# SCH_primary_recovery_n-3_board_2022-10-1.net
KiCad netlist of a schematic drawn in EasyEDA
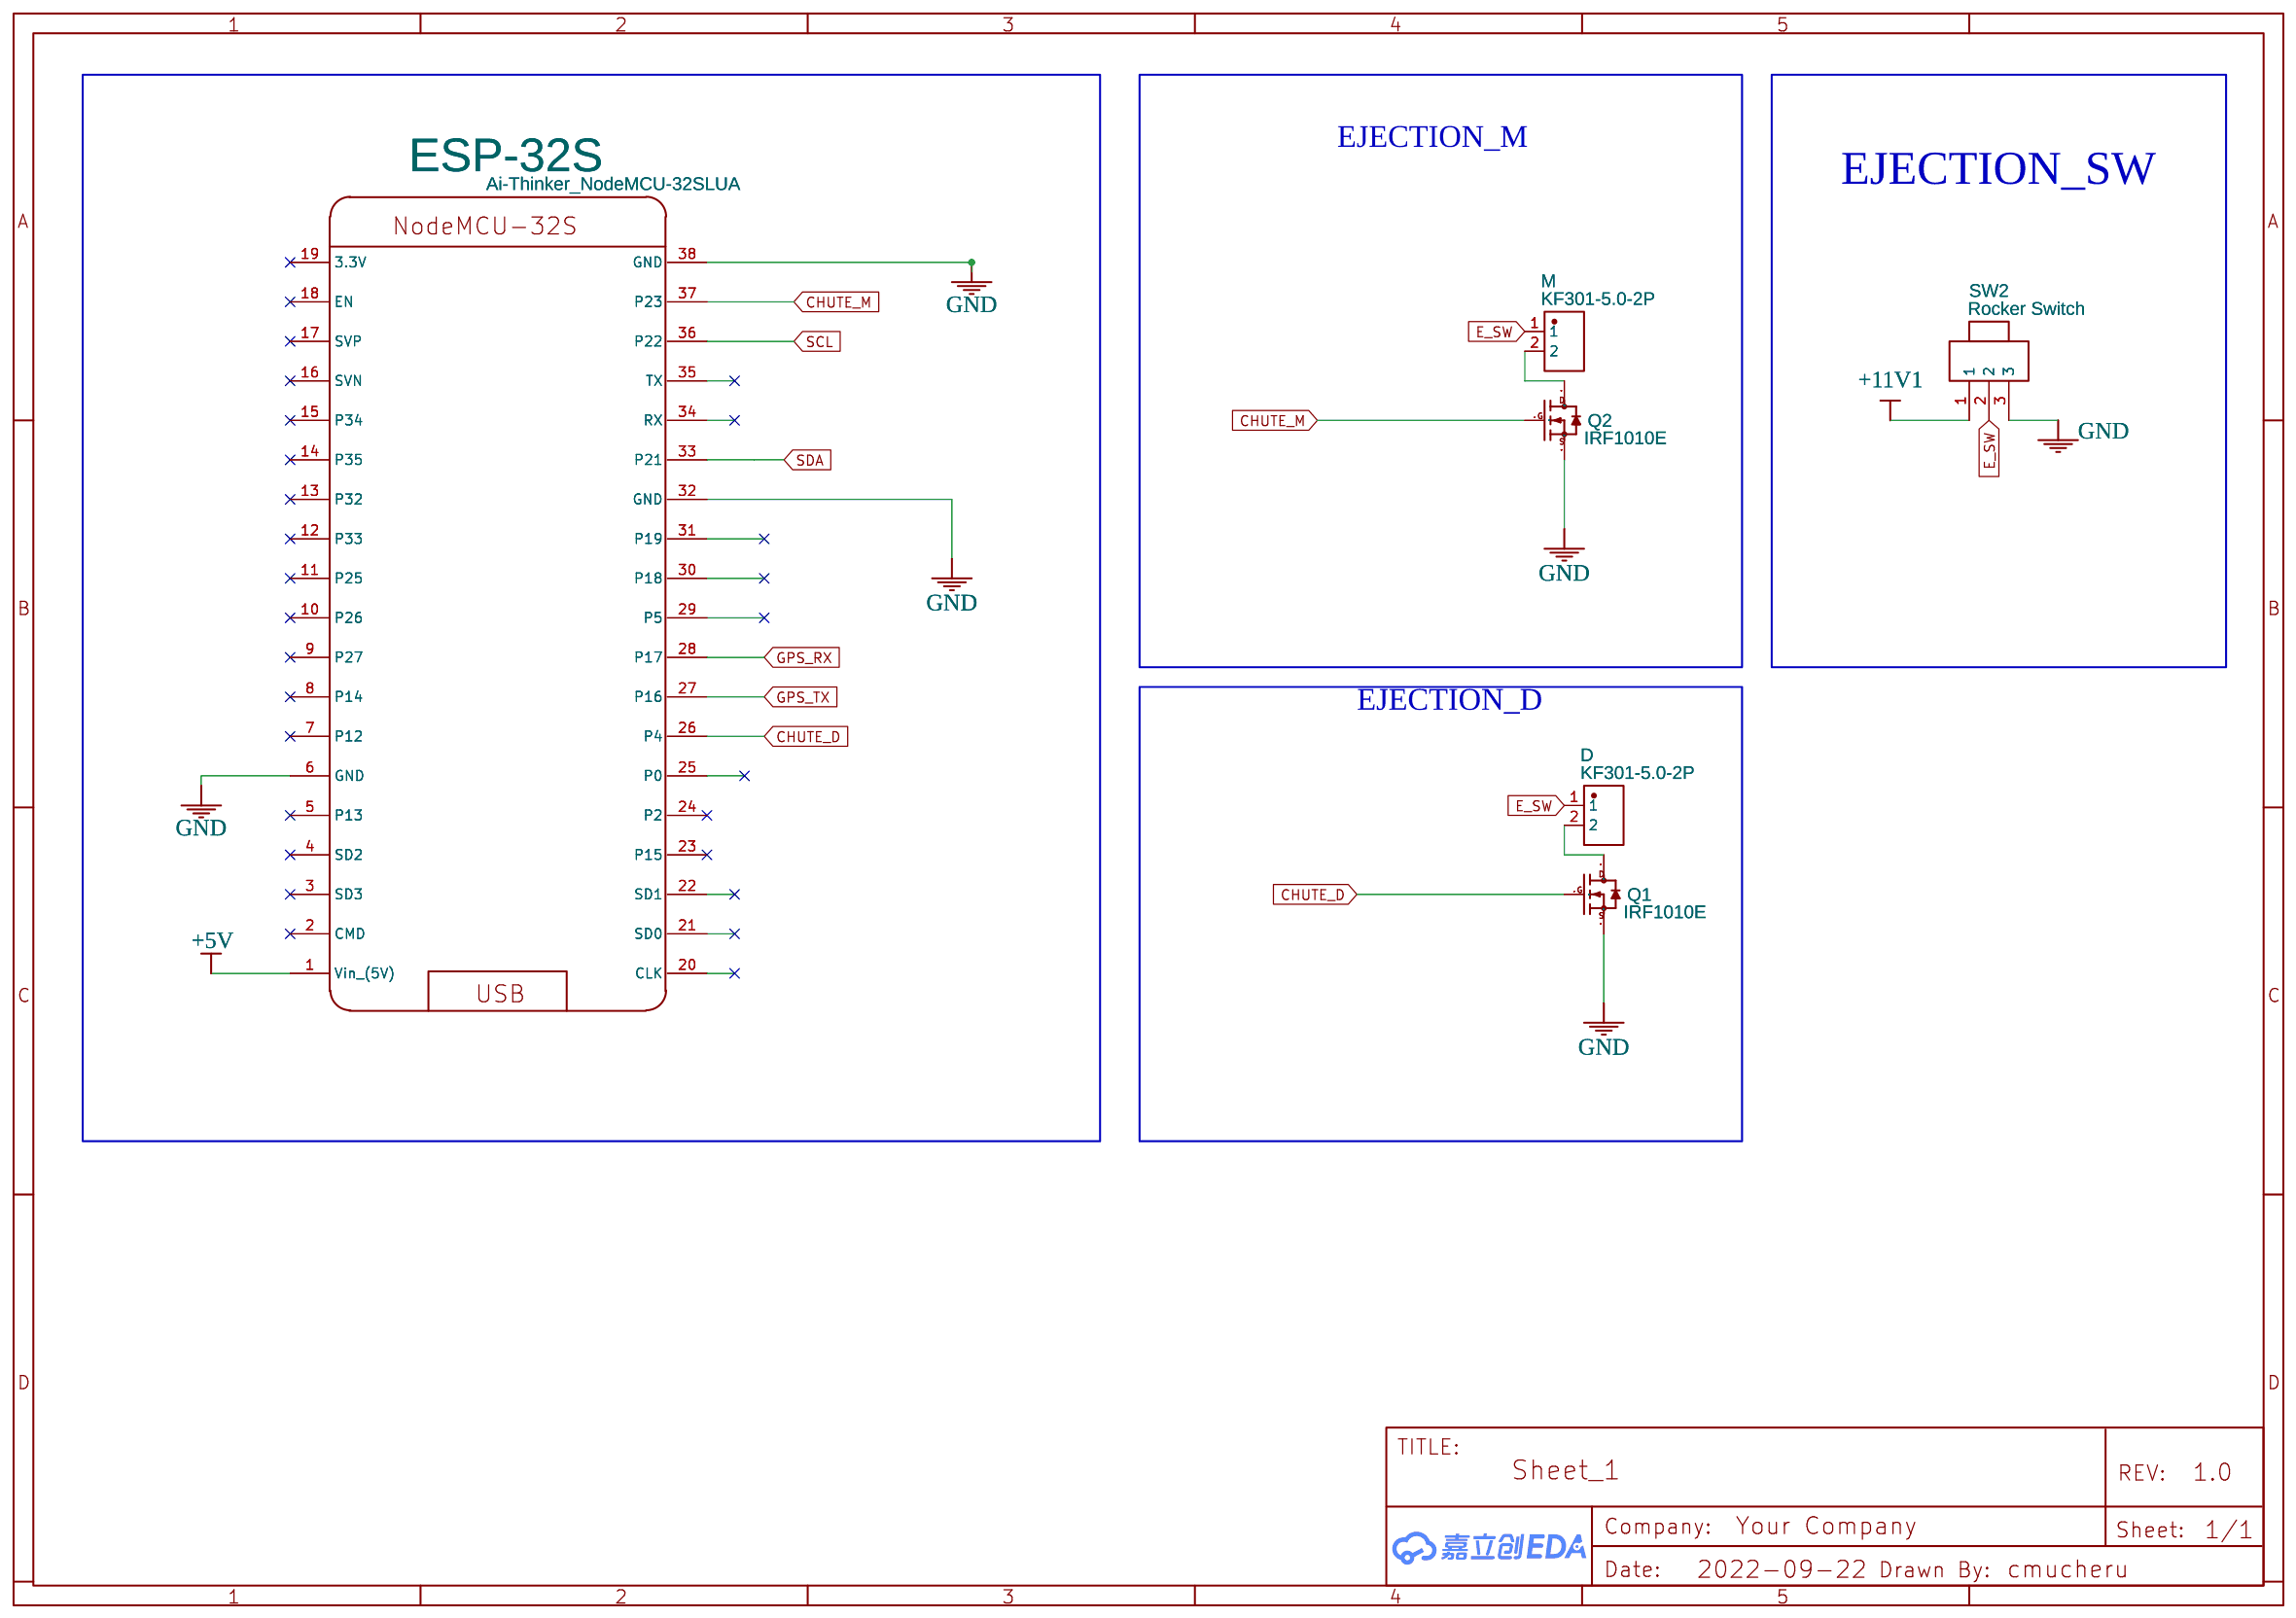
[diagram p0: Sheet_1]
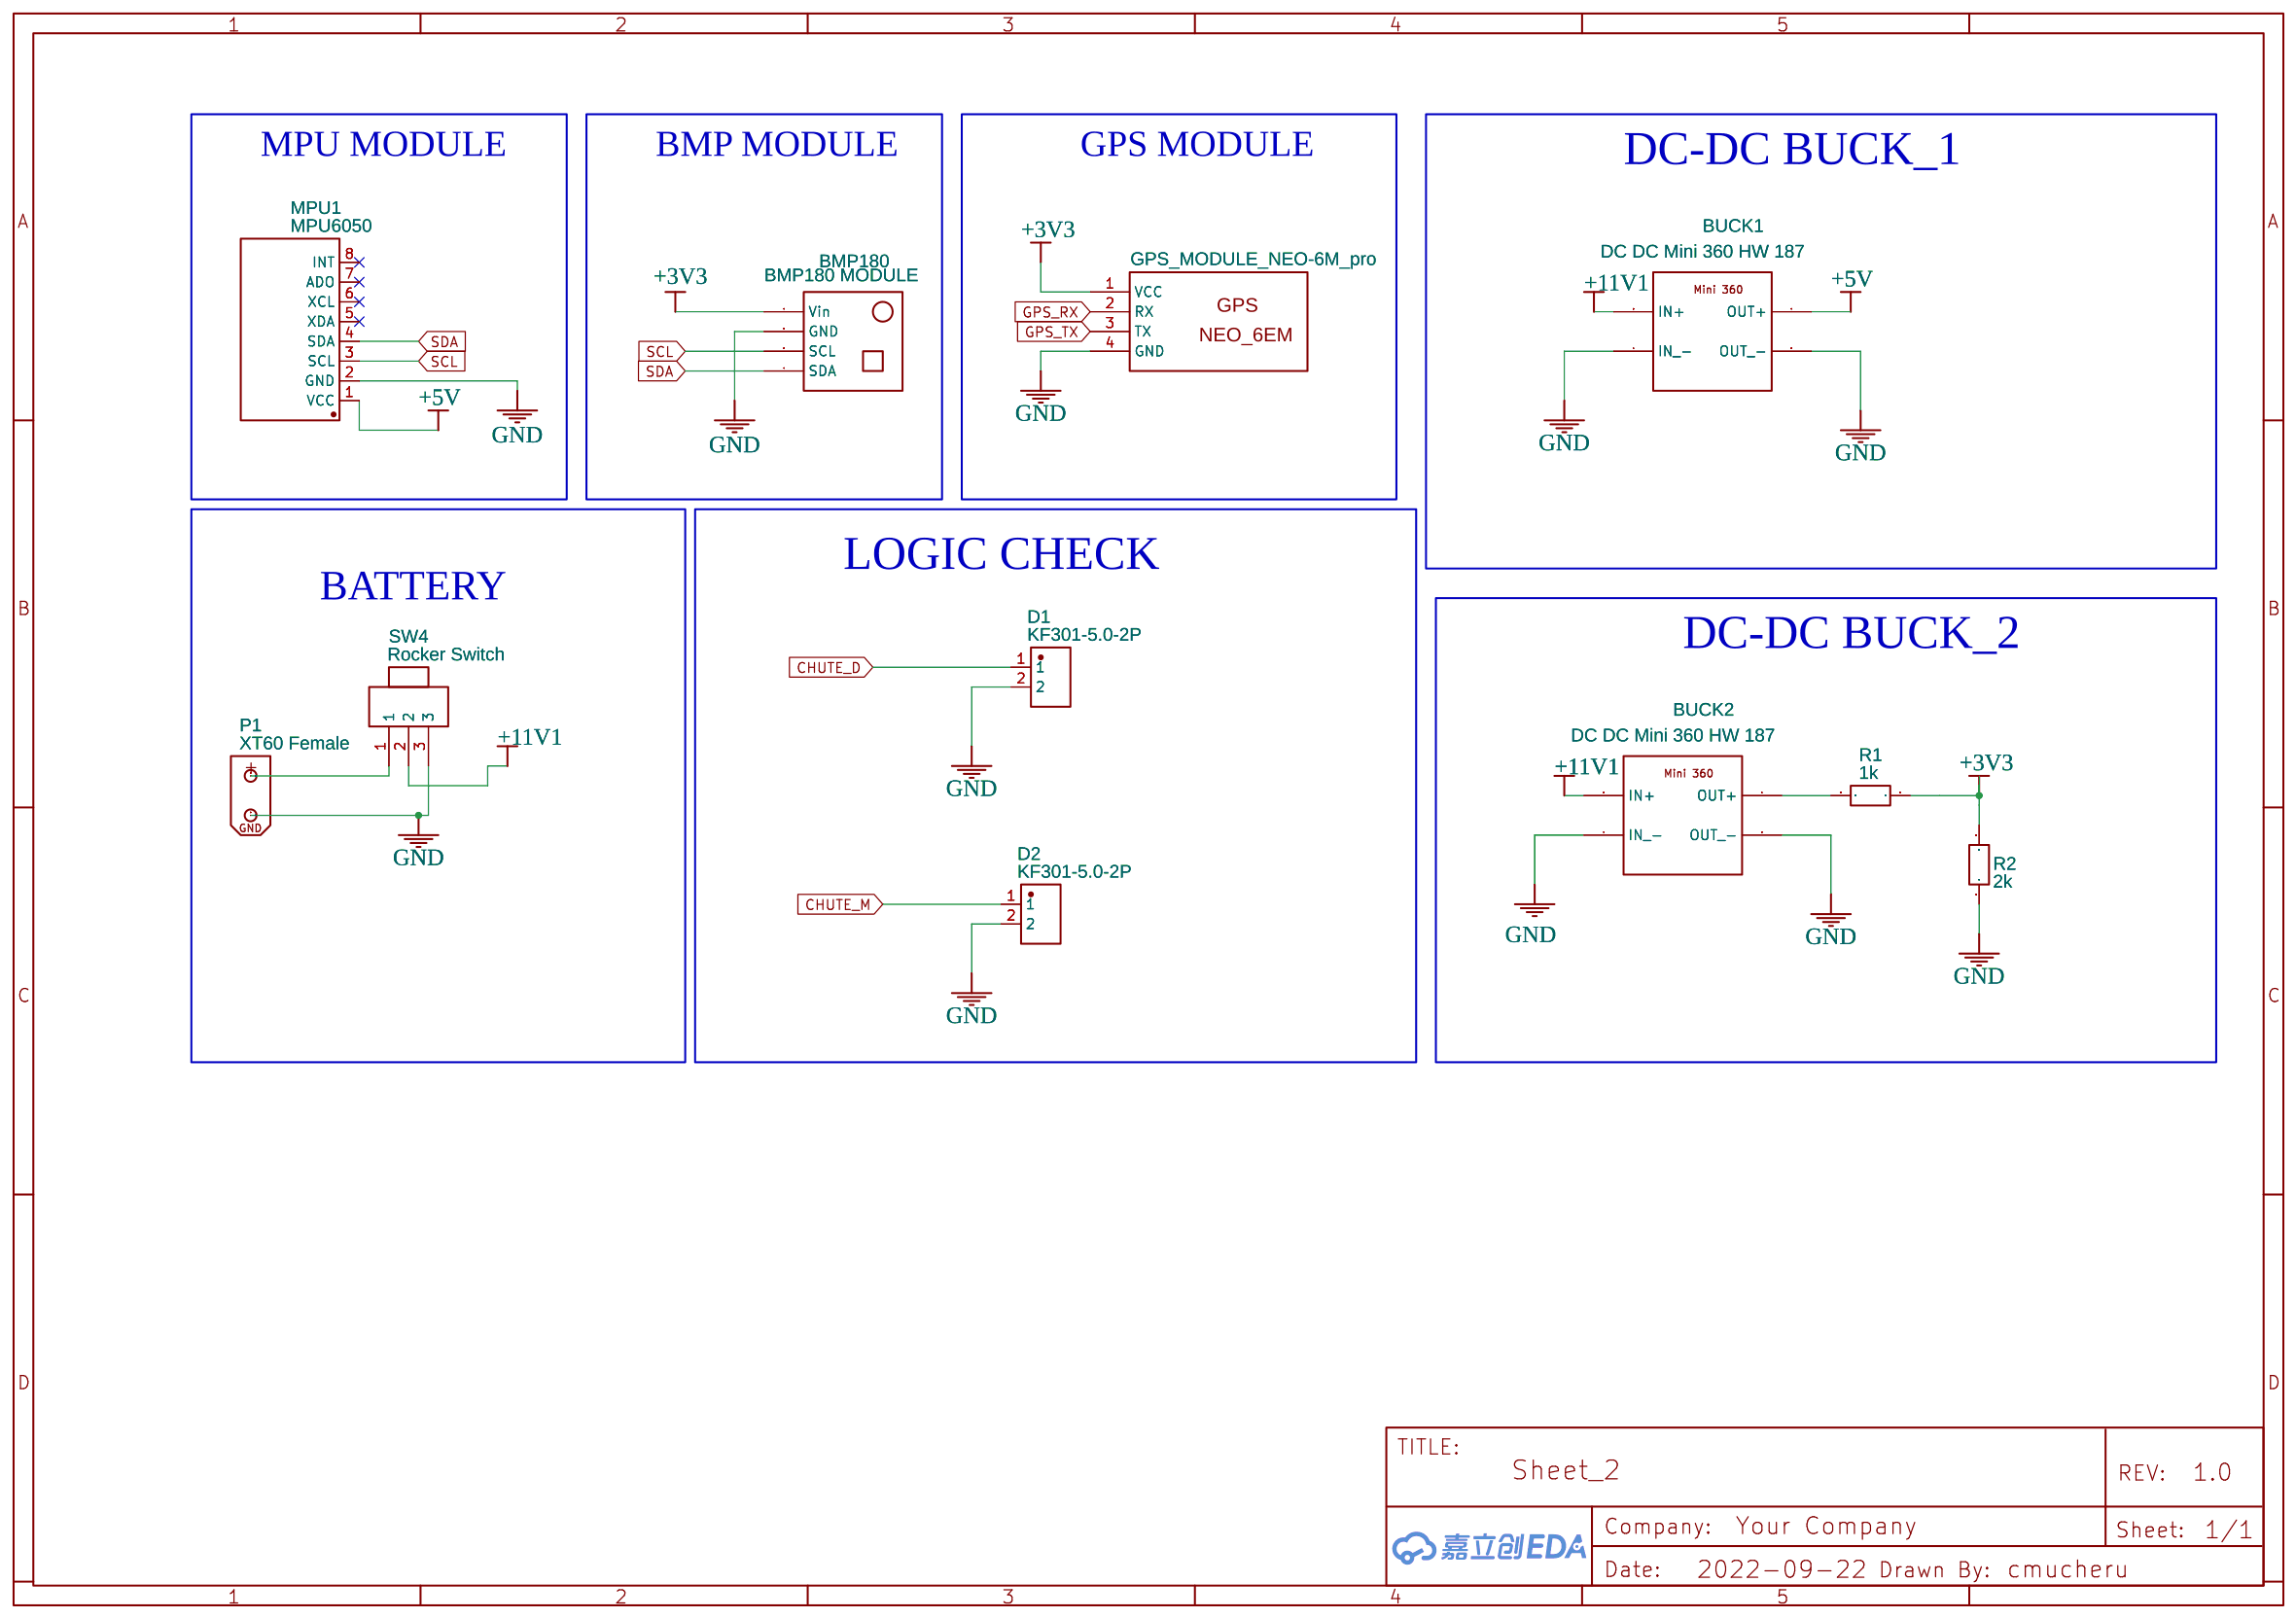
[diagram p1: Sheet_2]

(export (version "E")
  (design (tool "Eeschema 10.0.6"))
  (components
    (comp (ref "D")
      (value "KF301-5.0-2P")
      (fields (field (name "BOM_Supplier Part") "C474881"))
      (libsource (lib "") (part "KF301-5.0-2P_1"))
    )
    (comp (ref "ESP-32S")
      (value "Ai-Thinker_NodeMCU-32SLUA")
      (fields
        (field (name "BOM_Manufacturer Part") "NodeMCU-32SLua")
        (field (name "BOM_Supplier Part") "C111436")
      )
      (libsource (lib "") (part "Ai-Thinker_NodeMCU-32SLUA"))
    )
    (comp (ref "M")
      (value "KF301-5.0-2P")
      (fields (field (name "BOM_Supplier Part") "C474881"))
      (libsource (lib "") (part "KF301-5.0-2P"))
    )
    (comp (ref "Q1") (value "IRF1010E") (libsource (lib "") (part "Mosfet-N")))
    (comp (ref "Q2") (value "IRF1010E") (libsource (lib "") (part "Mosfet-N")))
    (comp (ref "SW2") (value "Rocker Switch") (libsource (lib "") (part "Rocker Switch")))
    (comp (ref "BMP180")
      (value "BMP180 MODULE")
      (fields (field (name "BOM_Manufacturer Part") "BMP180 (HW-596)"))
      (libsource (lib "") (part "BMP180 MODULE"))
    )
    (comp (ref "BUCK1") (value "DC DC Mini 360 HW 187") (libsource (lib "") (part "DC DC Mini 360 HW 187")))
    (comp (ref "BUCK2") (value "DC DC Mini 360 HW 187") (libsource (lib "") (part "DC DC Mini 360 HW 187")))
    (comp (ref "D1")
      (value "KF301-5.0-2P")
      (fields (field (name "BOM_Supplier Part") "C474881"))
      (libsource (lib "") (part "KF301-5.0-2P"))
    )
    (comp (ref "D2")
      (value "KF301-5.0-2P")
      (fields (field (name "BOM_Supplier Part") "C474881"))
      (libsource (lib "") (part "KF301-5.0-2P"))
    )
    (comp (ref "GPS_NEO-2EM")
      (value "GPS_MODULE_NEO-6M_pro")
      (libsource (lib "") (part "GPS_MODULE_NEO-6M_pro"))
    )
    (comp (ref "MPU1")
      (value "MPU6050")
      (fields (field (name "BOM_Supplier Part") "GY521"))
      (libsource (lib "") (part "MPU6050"))
    )
    (comp (ref "P1")
      (value "XT60 Female")
      (fields (field (name "BOM_Manufacturer Part") "XT60-F"))
      (libsource (lib "") (part "XT60 Female"))
    )
    (comp (ref "R1")
      (value "1k")
      (fields (field (name "BOM_Manufacturer Part") "OD684JE") (field (name "BOM_Supplier Part") "C3527706"))
      (libsource (lib "") (part "OD684JE_1"))
    )
    (comp (ref "R2")
      (value "2k")
      (fields (field (name "BOM_Manufacturer Part") "OD684JE") (field (name "BOM_Supplier Part") "C3527706"))
      (libsource (lib "") (part "OD684JE"))
    )
    (comp (ref "SW4") (value "Rocker Switch") (libsource (lib "") (part "Rocker Switch")))
  )
  (nets
    (net (code "1") (name "+3V3") (class "Default")
      (node (ref "BMP180") (pin "1") (pinfunction "Vin_1") (pintype "unspecified"))
      (node (ref "GPS_NEO-2EM") (pin "1") (pinfunction "VCC_1") (pintype "passive"))
      (node (ref "R1") (pin "1") (pinfunction "1_1") (pintype "unspecified"))
      (node (ref "R2") (pin "2") (pinfunction "2_2") (pintype "unspecified"))
    )
    (net (code "2") (name "+5V") (class "Default")
      (node (ref "BUCK1") (pin "1") (pinfunction "OUT+_1") (pintype "unspecified"))
      (node (ref "ESP-32S") (pin "1") (pinfunction "Vin_(5V)_1") (pintype "unspecified"))
      (node (ref "MPU1") (pin "1") (pinfunction "VCC_1") (pintype "unspecified"))
    )
    (net (code "3") (name "+11V1") (class "Default")
      (node (ref "BUCK1") (pin "3") (pinfunction "IN+_3") (pintype "unspecified"))
      (node (ref "BUCK2") (pin "3") (pinfunction "IN+_3") (pintype "unspecified"))
      (node (ref "SW2") (pin "1") (pinfunction "1_1") (pintype "unspecified"))
      (node (ref "SW4") (pin "2") (pinfunction "2_2") (pintype "unspecified"))
    )
    (net (code "4") (name "CHUTE_D") (class "Default")
      (node (ref "D1") (pin "1") (pinfunction "1_1") (pintype "unspecified"))
      (node (ref "ESP-32S") (pin "26") (pinfunction "P4_26") (pintype "unspecified"))
      (node (ref "Q1") (pin "1") (pinfunction "G_1") (pintype "unspecified"))
    )
    (net (code "5") (name "CHUTE_M") (class "Default")
      (node (ref "D2") (pin "1") (pinfunction "1_1") (pintype "unspecified"))
      (node (ref "ESP-32S") (pin "37") (pinfunction "P23_37") (pintype "unspecified"))
      (node (ref "Q2") (pin "1") (pinfunction "G_1") (pintype "unspecified"))
    )
    (net (code "6") (name "E_SW") (class "Default")
      (node (ref "D") (pin "1") (pinfunction "1_1") (pintype "unspecified"))
      (node (ref "M") (pin "1") (pinfunction "1_1") (pintype "unspecified"))
      (node (ref "SW2") (pin "2") (pinfunction "2_2") (pintype "unspecified"))
    )
    (net (code "7") (name "GND") (class "Default")
      (node (ref "BMP180") (pin "2") (pinfunction "GND_2") (pintype "unspecified"))
      (node (ref "BUCK1") (pin "2") (pinfunction "OUT_-_2") (pintype "unspecified"))
      (node (ref "BUCK1") (pin "4") (pinfunction "IN_-_4") (pintype "unspecified"))
      (node (ref "BUCK2") (pin "2") (pinfunction "OUT_-_2") (pintype "unspecified"))
      (node (ref "BUCK2") (pin "4") (pinfunction "IN_-_4") (pintype "unspecified"))
      (node (ref "D1") (pin "2") (pinfunction "2_2") (pintype "unspecified"))
      (node (ref "D2") (pin "2") (pinfunction "2_2") (pintype "unspecified"))
      (node (ref "ESP-32S") (pin "32") (pinfunction "GND_32") (pintype "unspecified"))
      (node (ref "ESP-32S") (pin "38") (pinfunction "GND_38") (pintype "unspecified"))
      (node (ref "ESP-32S") (pin "6") (pinfunction "GND_6") (pintype "unspecified"))
      (node (ref "GPS_NEO-2EM") (pin "4") (pinfunction "GND_4") (pintype "passive"))
      (node (ref "MPU1") (pin "2") (pinfunction "GND_2") (pintype "unspecified"))
      (node (ref "P1") (pin "1") (pinfunction "1_1") (pintype "unspecified"))
      (node (ref "Q1") (pin "3") (pinfunction "S_3") (pintype "unspecified"))
      (node (ref "Q2") (pin "3") (pinfunction "S_3") (pintype "unspecified"))
      (node (ref "R2") (pin "1") (pinfunction "1_1") (pintype "unspecified"))
      (node (ref "SW2") (pin "3") (pinfunction "3_3") (pintype "unspecified"))
      (node (ref "SW4") (pin "3") (pinfunction "3_3") (pintype "unspecified"))
    )
    (net (code "8") (name "GPS_RX") (class "Default")
      (node (ref "ESP-32S") (pin "28") (pinfunction "P17_28") (pintype "unspecified"))
      (node (ref "GPS_NEO-2EM") (pin "2") (pinfunction "RX_2") (pintype "input"))
    )
    (net (code "9") (name "GPS_TX") (class "Default")
      (node (ref "ESP-32S") (pin "27") (pinfunction "P16_27") (pintype "unspecified"))
      (node (ref "GPS_NEO-2EM") (pin "3") (pinfunction "TX_3") (pintype "output"))
    )
    (net (code "10") (name "Net-(BUCK2-OUT+)") (class "Default")
      (node (ref "BUCK2") (pin "1") (pinfunction "OUT+_1") (pintype "unspecified"))
      (node (ref "R1") (pin "2") (pinfunction "2_2") (pintype "unspecified"))
    )
    (net (code "11") (name "Net-(P1-Pad2)") (class "Default")
      (node (ref "P1") (pin "2") (pinfunction "2_2") (pintype "unspecified"))
      (node (ref "SW4") (pin "1") (pinfunction "1_1") (pintype "unspecified"))
    )
    (net (code "12") (name "Net-(Q1-D)") (class "Default")
      (node (ref "D") (pin "2") (pinfunction "2_2") (pintype "unspecified"))
      (node (ref "Q1") (pin "2") (pinfunction "D_2") (pintype "unspecified"))
    )
    (net (code "13") (name "Net-(Q2-D)") (class "Default")
      (node (ref "M") (pin "2") (pinfunction "2_2") (pintype "unspecified"))
      (node (ref "Q2") (pin "2") (pinfunction "D_2") (pintype "unspecified"))
    )
    (net (code "14") (name "SCL") (class "Default")
      (node (ref "BMP180") (pin "3") (pinfunction "SCL_3") (pintype "unspecified"))
      (node (ref "ESP-32S") (pin "36") (pinfunction "P22_36") (pintype "unspecified"))
      (node (ref "MPU1") (pin "3") (pinfunction "SCL_3") (pintype "unspecified"))
    )
    (net (code "15") (name "SDA") (class "Default")
      (node (ref "BMP180") (pin "4") (pinfunction "SDA_4") (pintype "unspecified"))
      (node (ref "ESP-32S") (pin "33") (pinfunction "P21_33") (pintype "unspecified"))
      (node (ref "MPU1") (pin "4") (pinfunction "SDA_4") (pintype "unspecified"))
    )
    (net (code "16") (name "unconnected-(ESP-32S-3.3V-Pad19)") (class "Default")
      (node (ref "ESP-32S") (pin "19") (pinfunction "3.3V_19") (pintype "unspecified+no_connect"))
    )
    (net (code "17") (name "unconnected-(ESP-32S-CLK-Pad20)") (class "Default")
      (node (ref "ESP-32S") (pin "20") (pinfunction "CLK_20") (pintype "unspecified+no_connect"))
    )
    (net (code "18") (name "unconnected-(ESP-32S-CMD-Pad2)") (class "Default")
      (node (ref "ESP-32S") (pin "2") (pinfunction "CMD_2") (pintype "unspecified+no_connect"))
    )
    (net (code "19") (name "unconnected-(ESP-32S-EN-Pad18)") (class "Default")
      (node (ref "ESP-32S") (pin "18") (pinfunction "EN_18") (pintype "unspecified+no_connect"))
    )
    (net (code "20") (name "unconnected-(ESP-32S-P0-Pad25)") (class "Default")
      (node (ref "ESP-32S") (pin "25") (pinfunction "P0_25") (pintype "unspecified+no_connect"))
    )
    (net (code "21") (name "unconnected-(ESP-32S-P2-Pad24)") (class "Default")
      (node (ref "ESP-32S") (pin "24") (pinfunction "P2_24") (pintype "unspecified+no_connect"))
    )
    (net (code "22") (name "unconnected-(ESP-32S-P5-Pad29)") (class "Default")
      (node (ref "ESP-32S") (pin "29") (pinfunction "P5_29") (pintype "unspecified+no_connect"))
    )
    (net (code "23") (name "unconnected-(ESP-32S-P12-Pad7)") (class "Default")
      (node (ref "ESP-32S") (pin "7") (pinfunction "P12_7") (pintype "unspecified+no_connect"))
    )
    (net (code "24") (name "unconnected-(ESP-32S-P13-Pad5)") (class "Default")
      (node (ref "ESP-32S") (pin "5") (pinfunction "P13_5") (pintype "unspecified+no_connect"))
    )
    (net (code "25") (name "unconnected-(ESP-32S-P14-Pad8)") (class "Default")
      (node (ref "ESP-32S") (pin "8") (pinfunction "P14_8") (pintype "unspecified+no_connect"))
    )
    (net (code "26") (name "unconnected-(ESP-32S-P15-Pad23)") (class "Default")
      (node (ref "ESP-32S") (pin "23") (pinfunction "P15_23") (pintype "unspecified+no_connect"))
    )
    (net (code "27") (name "unconnected-(ESP-32S-P18-Pad30)") (class "Default")
      (node (ref "ESP-32S") (pin "30") (pinfunction "P18_30") (pintype "unspecified+no_connect"))
    )
    (net (code "28") (name "unconnected-(ESP-32S-P19-Pad31)") (class "Default")
      (node (ref "ESP-32S") (pin "31") (pinfunction "P19_31") (pintype "unspecified+no_connect"))
    )
    (net (code "29") (name "unconnected-(ESP-32S-P25-Pad11)") (class "Default")
      (node (ref "ESP-32S") (pin "11") (pinfunction "P25_11") (pintype "unspecified+no_connect"))
    )
    (net (code "30") (name "unconnected-(ESP-32S-P26-Pad10)") (class "Default")
      (node (ref "ESP-32S") (pin "10") (pinfunction "P26_10") (pintype "unspecified+no_connect"))
    )
    (net (code "31") (name "unconnected-(ESP-32S-P27-Pad9)") (class "Default")
      (node (ref "ESP-32S") (pin "9") (pinfunction "P27_9") (pintype "unspecified+no_connect"))
    )
    (net (code "32") (name "unconnected-(ESP-32S-P32-Pad13)") (class "Default")
      (node (ref "ESP-32S") (pin "13") (pinfunction "P32_13") (pintype "unspecified+no_connect"))
    )
    (net (code "33") (name "unconnected-(ESP-32S-P33-Pad12)") (class "Default")
      (node (ref "ESP-32S") (pin "12") (pinfunction "P33_12") (pintype "unspecified+no_connect"))
    )
    (net (code "34") (name "unconnected-(ESP-32S-P34-Pad15)") (class "Default")
      (node (ref "ESP-32S") (pin "15") (pinfunction "P34_15") (pintype "unspecified+no_connect"))
    )
    (net (code "35") (name "unconnected-(ESP-32S-P35-Pad14)") (class "Default")
      (node (ref "ESP-32S") (pin "14") (pinfunction "P35_14") (pintype "unspecified+no_connect"))
    )
    (net (code "36") (name "unconnected-(ESP-32S-RX-Pad34)") (class "Default")
      (node (ref "ESP-32S") (pin "34") (pinfunction "RX_34") (pintype "unspecified+no_connect"))
    )
    (net (code "37") (name "unconnected-(ESP-32S-SD0-Pad21)") (class "Default")
      (node (ref "ESP-32S") (pin "21") (pinfunction "SD0_21") (pintype "unspecified+no_connect"))
    )
    (net (code "38") (name "unconnected-(ESP-32S-SD1-Pad22)") (class "Default")
      (node (ref "ESP-32S") (pin "22") (pinfunction "SD1_22") (pintype "unspecified+no_connect"))
    )
    (net (code "39") (name "unconnected-(ESP-32S-SD2-Pad4)") (class "Default")
      (node (ref "ESP-32S") (pin "4") (pinfunction "SD2_4") (pintype "unspecified+no_connect"))
    )
    (net (code "40") (name "unconnected-(ESP-32S-SD3-Pad3)") (class "Default")
      (node (ref "ESP-32S") (pin "3") (pinfunction "SD3_3") (pintype "unspecified+no_connect"))
    )
    (net (code "41") (name "unconnected-(ESP-32S-SVN-Pad16)") (class "Default")
      (node (ref "ESP-32S") (pin "16") (pinfunction "SVN_16") (pintype "unspecified+no_connect"))
    )
    (net (code "42") (name "unconnected-(ESP-32S-SVP-Pad17)") (class "Default")
      (node (ref "ESP-32S") (pin "17") (pinfunction "SVP_17") (pintype "unspecified+no_connect"))
    )
    (net (code "43") (name "unconnected-(ESP-32S-TX-Pad35)") (class "Default")
      (node (ref "ESP-32S") (pin "35") (pinfunction "TX_35") (pintype "unspecified+no_connect"))
    )
    (net (code "44") (name "unconnected-(MPU1-ADO-Pad7)") (class "Default")
      (node (ref "MPU1") (pin "7") (pinfunction "ADO_7") (pintype "unspecified+no_connect"))
    )
    (net (code "45") (name "unconnected-(MPU1-INT-Pad8)") (class "Default")
      (node (ref "MPU1") (pin "8") (pinfunction "INT_8") (pintype "unspecified+no_connect"))
    )
    (net (code "46") (name "unconnected-(MPU1-XCL-Pad6)") (class "Default")
      (node (ref "MPU1") (pin "6") (pinfunction "XCL_6") (pintype "unspecified+no_connect"))
    )
    (net (code "47") (name "unconnected-(MPU1-XDA-Pad5)") (class "Default")
      (node (ref "MPU1") (pin "5") (pinfunction "XDA_5") (pintype "unspecified+no_connect"))
    )
  )
)
